# ProPrj_FinalPatch_Design_2026-07-16.net
KiCad netlist of a schematic drawn in EasyEDA Pro
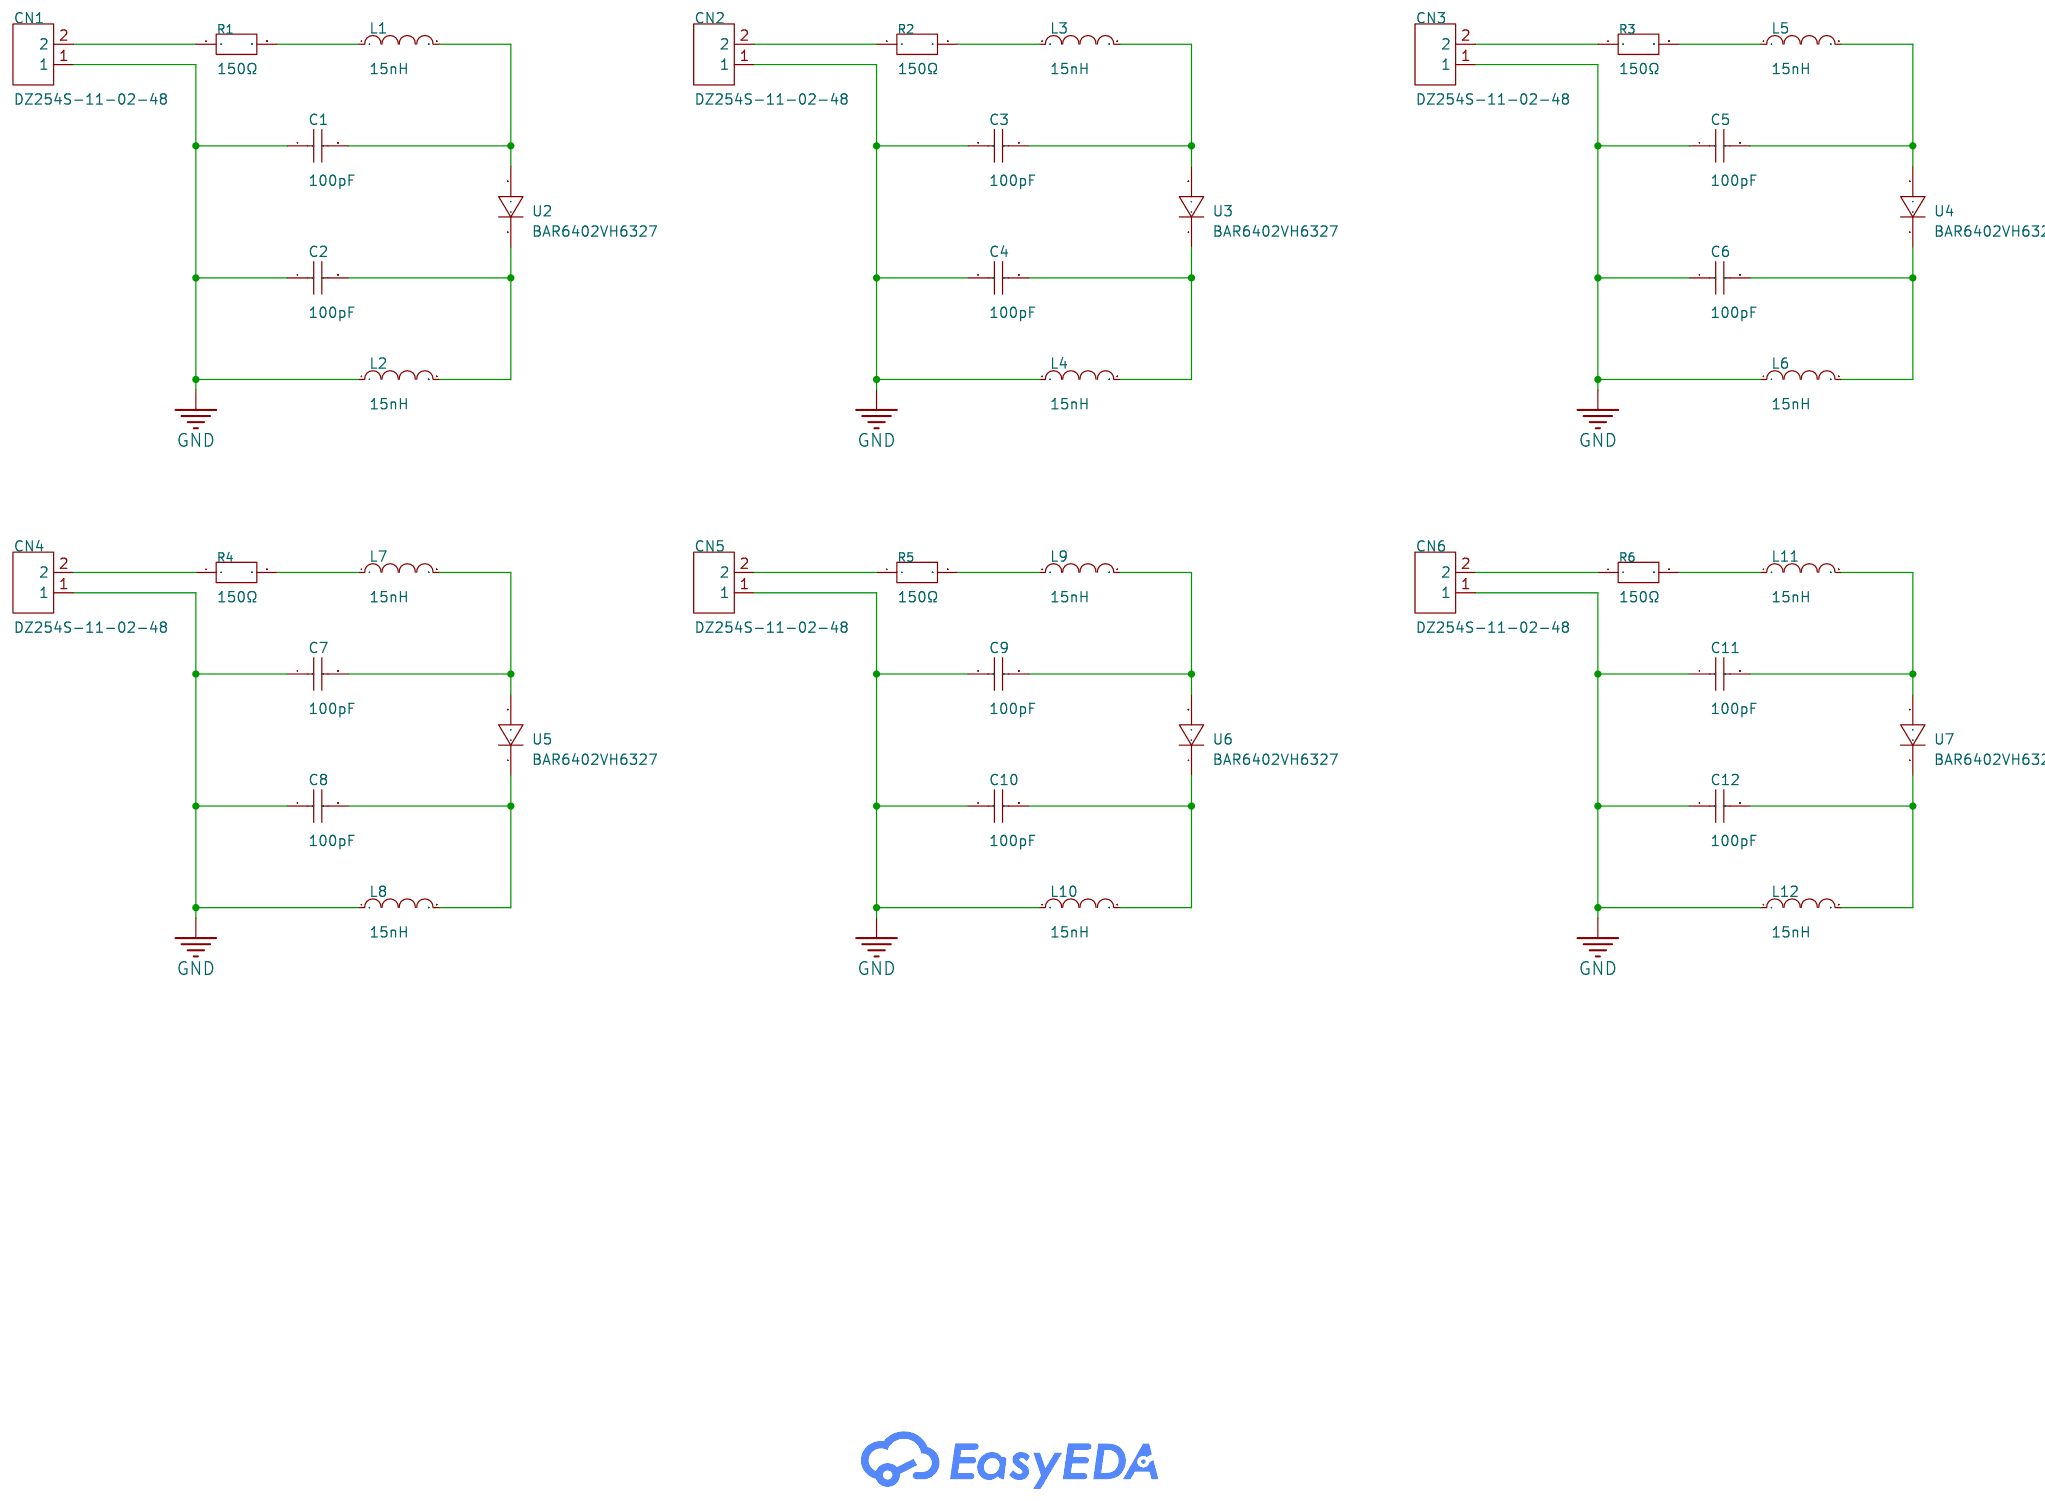
[diagram p0: schematic sheet]

(export (version "E")
  (design (tool "Eeschema 10.0.6"))
  (components
    (comp (ref "C1")
      (value "100pF")
      (footprint "easyedapro:C0402")
      (description "Capacitance:100pF Tolerance:±5% Tolerance:±5% Voltage Rating:50V Temperature Coefficient:C0G")
      (fields
        (field (name "Manufacturer Part") "GRM1555C1H101JA01D")
        (field (name "Manufacturer") "muRata(村田)")
      )
      (libsource (lib "easyedapro") (part "GRM1555C1H101JA01D"))
    )
    (comp (ref "C2")
      (value "100pF")
      (footprint "easyedapro:C0402")
      (description "Capacitance:100pF Tolerance:±5% Tolerance:±5% Voltage Rating:50V Temperature Coefficient:C0G")
      (fields
        (field (name "Manufacturer Part") "GRM1555C1H101JA01D")
        (field (name "Manufacturer") "muRata(村田)")
      )
      (libsource (lib "easyedapro") (part "GRM1555C1H101JA01D"))
    )
    (comp (ref "C3")
      (value "100pF")
      (footprint "easyedapro:C0402")
      (description "Capacitance:100pF Tolerance:±5% Tolerance:±5% Voltage Rating:50V Temperature Coefficient:C0G")
      (fields
        (field (name "Manufacturer Part") "GRM1555C1H101JA01D")
        (field (name "Manufacturer") "muRata(村田)")
      )
      (libsource (lib "easyedapro") (part "GRM1555C1H101JA01D"))
    )
    (comp (ref "C4")
      (value "100pF")
      (footprint "easyedapro:C0402")
      (description "Capacitance:100pF Tolerance:±5% Tolerance:±5% Voltage Rating:50V Temperature Coefficient:C0G")
      (fields
        (field (name "Manufacturer Part") "GRM1555C1H101JA01D")
        (field (name "Manufacturer") "muRata(村田)")
      )
      (libsource (lib "easyedapro") (part "GRM1555C1H101JA01D"))
    )
    (comp (ref "C5")
      (value "100pF")
      (footprint "easyedapro:C0402")
      (description "Capacitance:100pF Tolerance:±5% Tolerance:±5% Voltage Rating:50V Temperature Coefficient:C0G")
      (fields
        (field (name "Manufacturer Part") "GRM1555C1H101JA01D")
        (field (name "Manufacturer") "muRata(村田)")
      )
      (libsource (lib "easyedapro") (part "GRM1555C1H101JA01D"))
    )
    (comp (ref "C6")
      (value "100pF")
      (footprint "easyedapro:C0402")
      (description "Capacitance:100pF Tolerance:±5% Tolerance:±5% Voltage Rating:50V Temperature Coefficient:C0G")
      (fields
        (field (name "Manufacturer Part") "GRM1555C1H101JA01D")
        (field (name "Manufacturer") "muRata(村田)")
      )
      (libsource (lib "easyedapro") (part "GRM1555C1H101JA01D"))
    )
    (comp (ref "C7")
      (value "100pF")
      (footprint "easyedapro:C0402")
      (description "Capacitance:100pF Tolerance:±5% Tolerance:±5% Voltage Rating:50V Temperature Coefficient:C0G")
      (fields
        (field (name "Manufacturer Part") "GRM1555C1H101JA01D")
        (field (name "Manufacturer") "muRata(村田)")
      )
      (libsource (lib "easyedapro") (part "GRM1555C1H101JA01D"))
    )
    (comp (ref "C8")
      (value "100pF")
      (footprint "easyedapro:C0402")
      (description "Capacitance:100pF Tolerance:±5% Tolerance:±5% Voltage Rating:50V Temperature Coefficient:C0G")
      (fields
        (field (name "Manufacturer Part") "GRM1555C1H101JA01D")
        (field (name "Manufacturer") "muRata(村田)")
      )
      (libsource (lib "easyedapro") (part "GRM1555C1H101JA01D"))
    )
    (comp (ref "C9")
      (value "100pF")
      (footprint "easyedapro:C0402")
      (description "Capacitance:100pF Tolerance:±5% Tolerance:±5% Voltage Rating:50V Temperature Coefficient:C0G")
      (fields
        (field (name "Manufacturer Part") "GRM1555C1H101JA01D")
        (field (name "Manufacturer") "muRata(村田)")
      )
      (libsource (lib "easyedapro") (part "GRM1555C1H101JA01D"))
    )
    (comp (ref "C10")
      (value "100pF")
      (footprint "easyedapro:C0402")
      (description "Capacitance:100pF Tolerance:±5% Tolerance:±5% Voltage Rating:50V Temperature Coefficient:C0G")
      (fields
        (field (name "Manufacturer Part") "GRM1555C1H101JA01D")
        (field (name "Manufacturer") "muRata(村田)")
      )
      (libsource (lib "easyedapro") (part "GRM1555C1H101JA01D"))
    )
    (comp (ref "C11")
      (value "100pF")
      (footprint "easyedapro:C0402")
      (description "Capacitance:100pF Tolerance:±5% Tolerance:±5% Voltage Rating:50V Temperature Coefficient:C0G")
      (fields
        (field (name "Manufacturer Part") "GRM1555C1H101JA01D")
        (field (name "Manufacturer") "muRata(村田)")
      )
      (libsource (lib "easyedapro") (part "GRM1555C1H101JA01D"))
    )
    (comp (ref "C12")
      (value "100pF")
      (footprint "easyedapro:C0402")
      (description "Capacitance:100pF Tolerance:±5% Tolerance:±5% Voltage Rating:50V Temperature Coefficient:C0G")
      (fields
        (field (name "Manufacturer Part") "GRM1555C1H101JA01D")
        (field (name "Manufacturer") "muRata(村田)")
      )
      (libsource (lib "easyedapro") (part "GRM1555C1H101JA01D"))
    )
    (comp (ref "CN1")
      (value "DZ254S-11-02-48")
      (footprint "easyedapro:HDR-SMD_2P-P2.54-LS4.8")
      (fields (field (name "Manufacturer") "DEALON(德艺隆)"))
      (libsource (lib "easyedapro") (part "DZ254S-11-02-48"))
    )
    (comp (ref "CN2")
      (value "DZ254S-11-02-48")
      (footprint "easyedapro:HDR-SMD_2P-P2.54-LS4.8")
      (fields (field (name "Manufacturer") "DEALON(德艺隆)"))
      (libsource (lib "easyedapro") (part "DZ254S-11-02-48"))
    )
    (comp (ref "CN3")
      (value "DZ254S-11-02-48")
      (footprint "easyedapro:HDR-SMD_2P-P2.54-LS4.8")
      (fields (field (name "Manufacturer") "DEALON(德艺隆)"))
      (libsource (lib "easyedapro") (part "DZ254S-11-02-48"))
    )
    (comp (ref "CN4")
      (value "DZ254S-11-02-48")
      (footprint "easyedapro:HDR-SMD_2P-P2.54-LS4.8")
      (fields (field (name "Manufacturer") "DEALON(德艺隆)"))
      (libsource (lib "easyedapro") (part "DZ254S-11-02-48"))
    )
    (comp (ref "CN5")
      (value "DZ254S-11-02-48")
      (footprint "easyedapro:HDR-SMD_2P-P2.54-LS4.8")
      (fields (field (name "Manufacturer") "DEALON(德艺隆)"))
      (libsource (lib "easyedapro") (part "DZ254S-11-02-48"))
    )
    (comp (ref "CN6")
      (value "DZ254S-11-02-48")
      (footprint "easyedapro:HDR-SMD_2P-P2.54-LS4.8")
      (fields (field (name "Manufacturer") "DEALON(德艺隆)"))
      (libsource (lib "easyedapro") (part "DZ254S-11-02-48"))
    )
    (comp (ref "L1")
      (value "15nH")
      (footprint "easyedapro:IND-SMD_L1.0-W0.6")
      (fields (field (name "Manufacturer Part") "LQW15AN15NJ00D") (field (name "Manufacturer") "muRata(村田)"))
      (libsource (lib "easyedapro") (part "LQW15AN15NJ00D"))
    )
    (comp (ref "L2")
      (value "15nH")
      (footprint "easyedapro:IND-SMD_L1.0-W0.6")
      (fields (field (name "Manufacturer Part") "LQW15AN15NJ00D") (field (name "Manufacturer") "muRata(村田)"))
      (libsource (lib "easyedapro") (part "LQW15AN15NJ00D"))
    )
    (comp (ref "L3")
      (value "15nH")
      (footprint "easyedapro:IND-SMD_L1.0-W0.6")
      (fields (field (name "Manufacturer Part") "LQW15AN15NJ00D") (field (name "Manufacturer") "muRata(村田)"))
      (libsource (lib "easyedapro") (part "LQW15AN15NJ00D"))
    )
    (comp (ref "L4")
      (value "15nH")
      (footprint "easyedapro:IND-SMD_L1.0-W0.6")
      (fields (field (name "Manufacturer Part") "LQW15AN15NJ00D") (field (name "Manufacturer") "muRata(村田)"))
      (libsource (lib "easyedapro") (part "LQW15AN15NJ00D"))
    )
    (comp (ref "L5")
      (value "15nH")
      (footprint "easyedapro:IND-SMD_L1.0-W0.6")
      (fields (field (name "Manufacturer Part") "LQW15AN15NJ00D") (field (name "Manufacturer") "muRata(村田)"))
      (libsource (lib "easyedapro") (part "LQW15AN15NJ00D"))
    )
    (comp (ref "L6")
      (value "15nH")
      (footprint "easyedapro:IND-SMD_L1.0-W0.6")
      (fields (field (name "Manufacturer Part") "LQW15AN15NJ00D") (field (name "Manufacturer") "muRata(村田)"))
      (libsource (lib "easyedapro") (part "LQW15AN15NJ00D"))
    )
    (comp (ref "L7")
      (value "15nH")
      (footprint "easyedapro:IND-SMD_L1.0-W0.6")
      (fields (field (name "Manufacturer Part") "LQW15AN15NJ00D") (field (name "Manufacturer") "muRata(村田)"))
      (libsource (lib "easyedapro") (part "LQW15AN15NJ00D"))
    )
    (comp (ref "L8")
      (value "15nH")
      (footprint "easyedapro:IND-SMD_L1.0-W0.6")
      (fields (field (name "Manufacturer Part") "LQW15AN15NJ00D") (field (name "Manufacturer") "muRata(村田)"))
      (libsource (lib "easyedapro") (part "LQW15AN15NJ00D"))
    )
    (comp (ref "L9")
      (value "15nH")
      (footprint "easyedapro:IND-SMD_L1.0-W0.6")
      (fields (field (name "Manufacturer Part") "LQW15AN15NJ00D") (field (name "Manufacturer") "muRata(村田)"))
      (libsource (lib "easyedapro") (part "LQW15AN15NJ00D"))
    )
    (comp (ref "L10")
      (value "15nH")
      (footprint "easyedapro:IND-SMD_L1.0-W0.6")
      (fields (field (name "Manufacturer Part") "LQW15AN15NJ00D") (field (name "Manufacturer") "muRata(村田)"))
      (libsource (lib "easyedapro") (part "LQW15AN15NJ00D"))
    )
    (comp (ref "L11")
      (value "15nH")
      (footprint "easyedapro:IND-SMD_L1.0-W0.6")
      (fields (field (name "Manufacturer Part") "LQW15AN15NJ00D") (field (name "Manufacturer") "muRata(村田)"))
      (libsource (lib "easyedapro") (part "LQW15AN15NJ00D"))
    )
    (comp (ref "L12")
      (value "15nH")
      (footprint "easyedapro:IND-SMD_L1.0-W0.6")
      (fields (field (name "Manufacturer Part") "LQW15AN15NJ00D") (field (name "Manufacturer") "muRata(村田)"))
      (libsource (lib "easyedapro") (part "LQW15AN15NJ00D"))
    )
    (comp (ref "R1")
      (value "150Ω")
      (footprint "easyedapro:R0603")
      (fields
        (field (name "Manufacturer Part") "HP03W5F1500T5E")
        (field (name "Manufacturer") "UNI-ROYAL(厚声)")
      )
      (libsource (lib "easyedapro") (part "HP03W5F1500T5E"))
    )
    (comp (ref "R2")
      (value "150Ω")
      (footprint "easyedapro:R0603")
      (fields
        (field (name "Manufacturer Part") "HP03W5F1500T5E")
        (field (name "Manufacturer") "UNI-ROYAL(厚声)")
      )
      (libsource (lib "easyedapro") (part "HP03W5F1500T5E"))
    )
    (comp (ref "R3")
      (value "150Ω")
      (footprint "easyedapro:R0603")
      (fields
        (field (name "Manufacturer Part") "HP03W5F1500T5E")
        (field (name "Manufacturer") "UNI-ROYAL(厚声)")
      )
      (libsource (lib "easyedapro") (part "HP03W5F1500T5E"))
    )
    (comp (ref "R4")
      (value "150Ω")
      (footprint "easyedapro:R0603")
      (fields
        (field (name "Manufacturer Part") "HP03W5F1500T5E")
        (field (name "Manufacturer") "UNI-ROYAL(厚声)")
      )
      (libsource (lib "easyedapro") (part "HP03W5F1500T5E"))
    )
    (comp (ref "R5")
      (value "150Ω")
      (footprint "easyedapro:R0603")
      (fields
        (field (name "Manufacturer Part") "HP03W5F1500T5E")
        (field (name "Manufacturer") "UNI-ROYAL(厚声)")
      )
      (libsource (lib "easyedapro") (part "HP03W5F1500T5E"))
    )
    (comp (ref "R6")
      (value "150Ω")
      (footprint "easyedapro:R0603")
      (fields
        (field (name "Manufacturer Part") "HP03W5F1500T5E")
        (field (name "Manufacturer") "UNI-ROYAL(厚声)")
      )
      (libsource (lib "easyedapro") (part "HP03W5F1500T5E"))
    )
    (comp (ref "U2")
      (value "BAR6402VH6327")
      (footprint "easyedapro:SC-79_L1.2-W0.8-LS1.6-RD")
      (fields (field (name "Manufacturer") "Infineon(英飞凌)"))
      (libsource (lib "easyedapro") (part "BAR6402VH6327XTSA1"))
    )
    (comp (ref "U3")
      (value "BAR6402VH6327")
      (footprint "easyedapro:SC-79_L1.2-W0.8-LS1.6-RD")
      (fields (field (name "Manufacturer") "Infineon(英飞凌)"))
      (libsource (lib "easyedapro") (part "BAR6402VH6327XTSA1"))
    )
    (comp (ref "U4")
      (value "BAR6402VH6327")
      (footprint "easyedapro:SC-79_L1.2-W0.8-LS1.6-RD")
      (fields (field (name "Manufacturer") "Infineon(英飞凌)"))
      (libsource (lib "easyedapro") (part "BAR6402VH6327XTSA1"))
    )
    (comp (ref "U5")
      (value "BAR6402VH6327")
      (footprint "easyedapro:SC-79_L1.2-W0.8-LS1.6-RD")
      (fields (field (name "Manufacturer") "Infineon(英飞凌)"))
      (libsource (lib "easyedapro") (part "BAR6402VH6327XTSA1"))
    )
    (comp (ref "U6")
      (value "BAR6402VH6327")
      (footprint "easyedapro:SC-79_L1.2-W0.8-LS1.6-RD")
      (fields (field (name "Manufacturer") "Infineon(英飞凌)"))
      (libsource (lib "easyedapro") (part "BAR6402VH6327XTSA1"))
    )
    (comp (ref "U7")
      (value "BAR6402VH6327")
      (footprint "easyedapro:SC-79_L1.2-W0.8-LS1.6-RD")
      (fields (field (name "Manufacturer") "Infineon(英飞凌)"))
      (libsource (lib "easyedapro") (part "BAR6402VH6327XTSA1"))
    )
  )
  (nets
    (net (code "1") (name "GND") (class "Default")
      (node (ref "C1") (pin "1") (pinfunction "1_1") (pintype "input"))
      (node (ref "C10") (pin "1") (pinfunction "1_1") (pintype "input"))
      (node (ref "C11") (pin "1") (pinfunction "1_1") (pintype "input"))
      (node (ref "C12") (pin "1") (pinfunction "1_1") (pintype "input"))
      (node (ref "C2") (pin "1") (pinfunction "1_1") (pintype "input"))
      (node (ref "C3") (pin "1") (pinfunction "1_1") (pintype "input"))
      (node (ref "C4") (pin "1") (pinfunction "1_1") (pintype "input"))
      (node (ref "C5") (pin "1") (pinfunction "1_1") (pintype "input"))
      (node (ref "C6") (pin "1") (pinfunction "1_1") (pintype "input"))
      (node (ref "C7") (pin "1") (pinfunction "1_1") (pintype "input"))
      (node (ref "C8") (pin "1") (pinfunction "1_1") (pintype "input"))
      (node (ref "C9") (pin "1") (pinfunction "1_1") (pintype "input"))
      (node (ref "CN1") (pin "1") (pinfunction "1_1") (pintype "unspecified"))
      (node (ref "CN2") (pin "1") (pinfunction "1_1") (pintype "unspecified"))
      (node (ref "CN3") (pin "1") (pinfunction "1_1") (pintype "unspecified"))
      (node (ref "CN4") (pin "1") (pinfunction "1_1") (pintype "unspecified"))
      (node (ref "CN5") (pin "1") (pinfunction "1_1") (pintype "unspecified"))
      (node (ref "CN6") (pin "1") (pinfunction "1_1") (pintype "unspecified"))
      (node (ref "L10") (pin "1") (pinfunction "1_1") (pintype "unspecified"))
      (node (ref "L12") (pin "1") (pinfunction "1_1") (pintype "unspecified"))
      (node (ref "L2") (pin "1") (pinfunction "1_1") (pintype "unspecified"))
      (node (ref "L4") (pin "1") (pinfunction "1_1") (pintype "unspecified"))
      (node (ref "L6") (pin "1") (pinfunction "1_1") (pintype "unspecified"))
      (node (ref "L8") (pin "1") (pinfunction "1_1") (pintype "unspecified"))
    )
    (net (code "2") (name "Net-(CN1-Pad2)") (class "Default")
      (node (ref "CN1") (pin "2") (pinfunction "2_2") (pintype "unspecified"))
      (node (ref "R1") (pin "1") (pinfunction "1_1") (pintype "input"))
    )
    (net (code "3") (name "Net-(CN2-Pad2)") (class "Default")
      (node (ref "CN2") (pin "2") (pinfunction "2_2") (pintype "unspecified"))
      (node (ref "R2") (pin "1") (pinfunction "1_1") (pintype "input"))
    )
    (net (code "4") (name "Net-(CN3-Pad2)") (class "Default")
      (node (ref "CN3") (pin "2") (pinfunction "2_2") (pintype "unspecified"))
      (node (ref "R3") (pin "1") (pinfunction "1_1") (pintype "input"))
    )
    (net (code "5") (name "Net-(CN4-Pad2)") (class "Default")
      (node (ref "CN4") (pin "2") (pinfunction "2_2") (pintype "unspecified"))
      (node (ref "R4") (pin "1") (pinfunction "1_1") (pintype "input"))
    )
    (net (code "6") (name "Net-(CN5-Pad2)") (class "Default")
      (node (ref "CN5") (pin "2") (pinfunction "2_2") (pintype "unspecified"))
      (node (ref "R5") (pin "1") (pinfunction "1_1") (pintype "input"))
    )
    (net (code "7") (name "Net-(CN6-Pad2)") (class "Default")
      (node (ref "CN6") (pin "2") (pinfunction "2_2") (pintype "unspecified"))
      (node (ref "R6") (pin "1") (pinfunction "1_1") (pintype "input"))
    )
    (net (code "8") (name "Net-(L1-Pad1)") (class "Default")
      (node (ref "L1") (pin "1") (pinfunction "1_1") (pintype "unspecified"))
      (node (ref "R1") (pin "2") (pinfunction "2_2") (pintype "input"))
    )
    (net (code "9") (name "Net-(L3-Pad1)") (class "Default")
      (node (ref "L3") (pin "1") (pinfunction "1_1") (pintype "unspecified"))
      (node (ref "R2") (pin "2") (pinfunction "2_2") (pintype "input"))
    )
    (net (code "10") (name "Net-(L5-Pad1)") (class "Default")
      (node (ref "L5") (pin "1") (pinfunction "1_1") (pintype "unspecified"))
      (node (ref "R3") (pin "2") (pinfunction "2_2") (pintype "input"))
    )
    (net (code "11") (name "Net-(L7-Pad1)") (class "Default")
      (node (ref "L7") (pin "1") (pinfunction "1_1") (pintype "unspecified"))
      (node (ref "R4") (pin "2") (pinfunction "2_2") (pintype "input"))
    )
    (net (code "12") (name "Net-(L9-Pad1)") (class "Default")
      (node (ref "L9") (pin "1") (pinfunction "1_1") (pintype "unspecified"))
      (node (ref "R5") (pin "2") (pinfunction "2_2") (pintype "input"))
    )
    (net (code "13") (name "Net-(L11-Pad1)") (class "Default")
      (node (ref "L11") (pin "1") (pinfunction "1_1") (pintype "unspecified"))
      (node (ref "R6") (pin "2") (pinfunction "2_2") (pintype "input"))
    )
    (net (code "14") (name "Net-(U2-A)") (class "Default")
      (node (ref "C2") (pin "2") (pinfunction "2_2") (pintype "input"))
      (node (ref "L2") (pin "2") (pinfunction "2_2") (pintype "unspecified"))
      (node (ref "U2") (pin "1") (pinfunction "A_1") (pintype "unspecified"))
    )
    (net (code "15") (name "Net-(U2-K)") (class "Default")
      (node (ref "C1") (pin "2") (pinfunction "2_2") (pintype "input"))
      (node (ref "L1") (pin "2") (pinfunction "2_2") (pintype "unspecified"))
      (node (ref "U2") (pin "2") (pinfunction "K_2") (pintype "unspecified"))
    )
    (net (code "16") (name "Net-(U3-A)") (class "Default")
      (node (ref "C4") (pin "2") (pinfunction "2_2") (pintype "input"))
      (node (ref "L4") (pin "2") (pinfunction "2_2") (pintype "unspecified"))
      (node (ref "U3") (pin "1") (pinfunction "A_1") (pintype "unspecified"))
    )
    (net (code "17") (name "Net-(U3-K)") (class "Default")
      (node (ref "C3") (pin "2") (pinfunction "2_2") (pintype "input"))
      (node (ref "L3") (pin "2") (pinfunction "2_2") (pintype "unspecified"))
      (node (ref "U3") (pin "2") (pinfunction "K_2") (pintype "unspecified"))
    )
    (net (code "18") (name "Net-(U4-A)") (class "Default")
      (node (ref "C6") (pin "2") (pinfunction "2_2") (pintype "input"))
      (node (ref "L6") (pin "2") (pinfunction "2_2") (pintype "unspecified"))
      (node (ref "U4") (pin "1") (pinfunction "A_1") (pintype "unspecified"))
    )
    (net (code "19") (name "Net-(U4-K)") (class "Default")
      (node (ref "C5") (pin "2") (pinfunction "2_2") (pintype "input"))
      (node (ref "L5") (pin "2") (pinfunction "2_2") (pintype "unspecified"))
      (node (ref "U4") (pin "2") (pinfunction "K_2") (pintype "unspecified"))
    )
    (net (code "20") (name "Net-(U5-A)") (class "Default")
      (node (ref "C8") (pin "2") (pinfunction "2_2") (pintype "input"))
      (node (ref "L8") (pin "2") (pinfunction "2_2") (pintype "unspecified"))
      (node (ref "U5") (pin "1") (pinfunction "A_1") (pintype "unspecified"))
    )
    (net (code "21") (name "Net-(U5-K)") (class "Default")
      (node (ref "C7") (pin "2") (pinfunction "2_2") (pintype "input"))
      (node (ref "L7") (pin "2") (pinfunction "2_2") (pintype "unspecified"))
      (node (ref "U5") (pin "2") (pinfunction "K_2") (pintype "unspecified"))
    )
    (net (code "22") (name "Net-(U6-A)") (class "Default")
      (node (ref "C10") (pin "2") (pinfunction "2_2") (pintype "input"))
      (node (ref "L10") (pin "2") (pinfunction "2_2") (pintype "unspecified"))
      (node (ref "U6") (pin "1") (pinfunction "A_1") (pintype "unspecified"))
    )
    (net (code "23") (name "Net-(U6-K)") (class "Default")
      (node (ref "C9") (pin "2") (pinfunction "2_2") (pintype "input"))
      (node (ref "L9") (pin "2") (pinfunction "2_2") (pintype "unspecified"))
      (node (ref "U6") (pin "2") (pinfunction "K_2") (pintype "unspecified"))
    )
    (net (code "24") (name "Net-(U7-A)") (class "Default")
      (node (ref "C12") (pin "2") (pinfunction "2_2") (pintype "input"))
      (node (ref "L12") (pin "2") (pinfunction "2_2") (pintype "unspecified"))
      (node (ref "U7") (pin "1") (pinfunction "A_1") (pintype "unspecified"))
    )
    (net (code "25") (name "Net-(U7-K)") (class "Default")
      (node (ref "C11") (pin "2") (pinfunction "2_2") (pintype "input"))
      (node (ref "L11") (pin "2") (pinfunction "2_2") (pintype "unspecified"))
      (node (ref "U7") (pin "2") (pinfunction "K_2") (pintype "unspecified"))
    )
  )
)
